# I2C_motor_controller.net
KiCad netlist of a schematic drawn in EAGLE
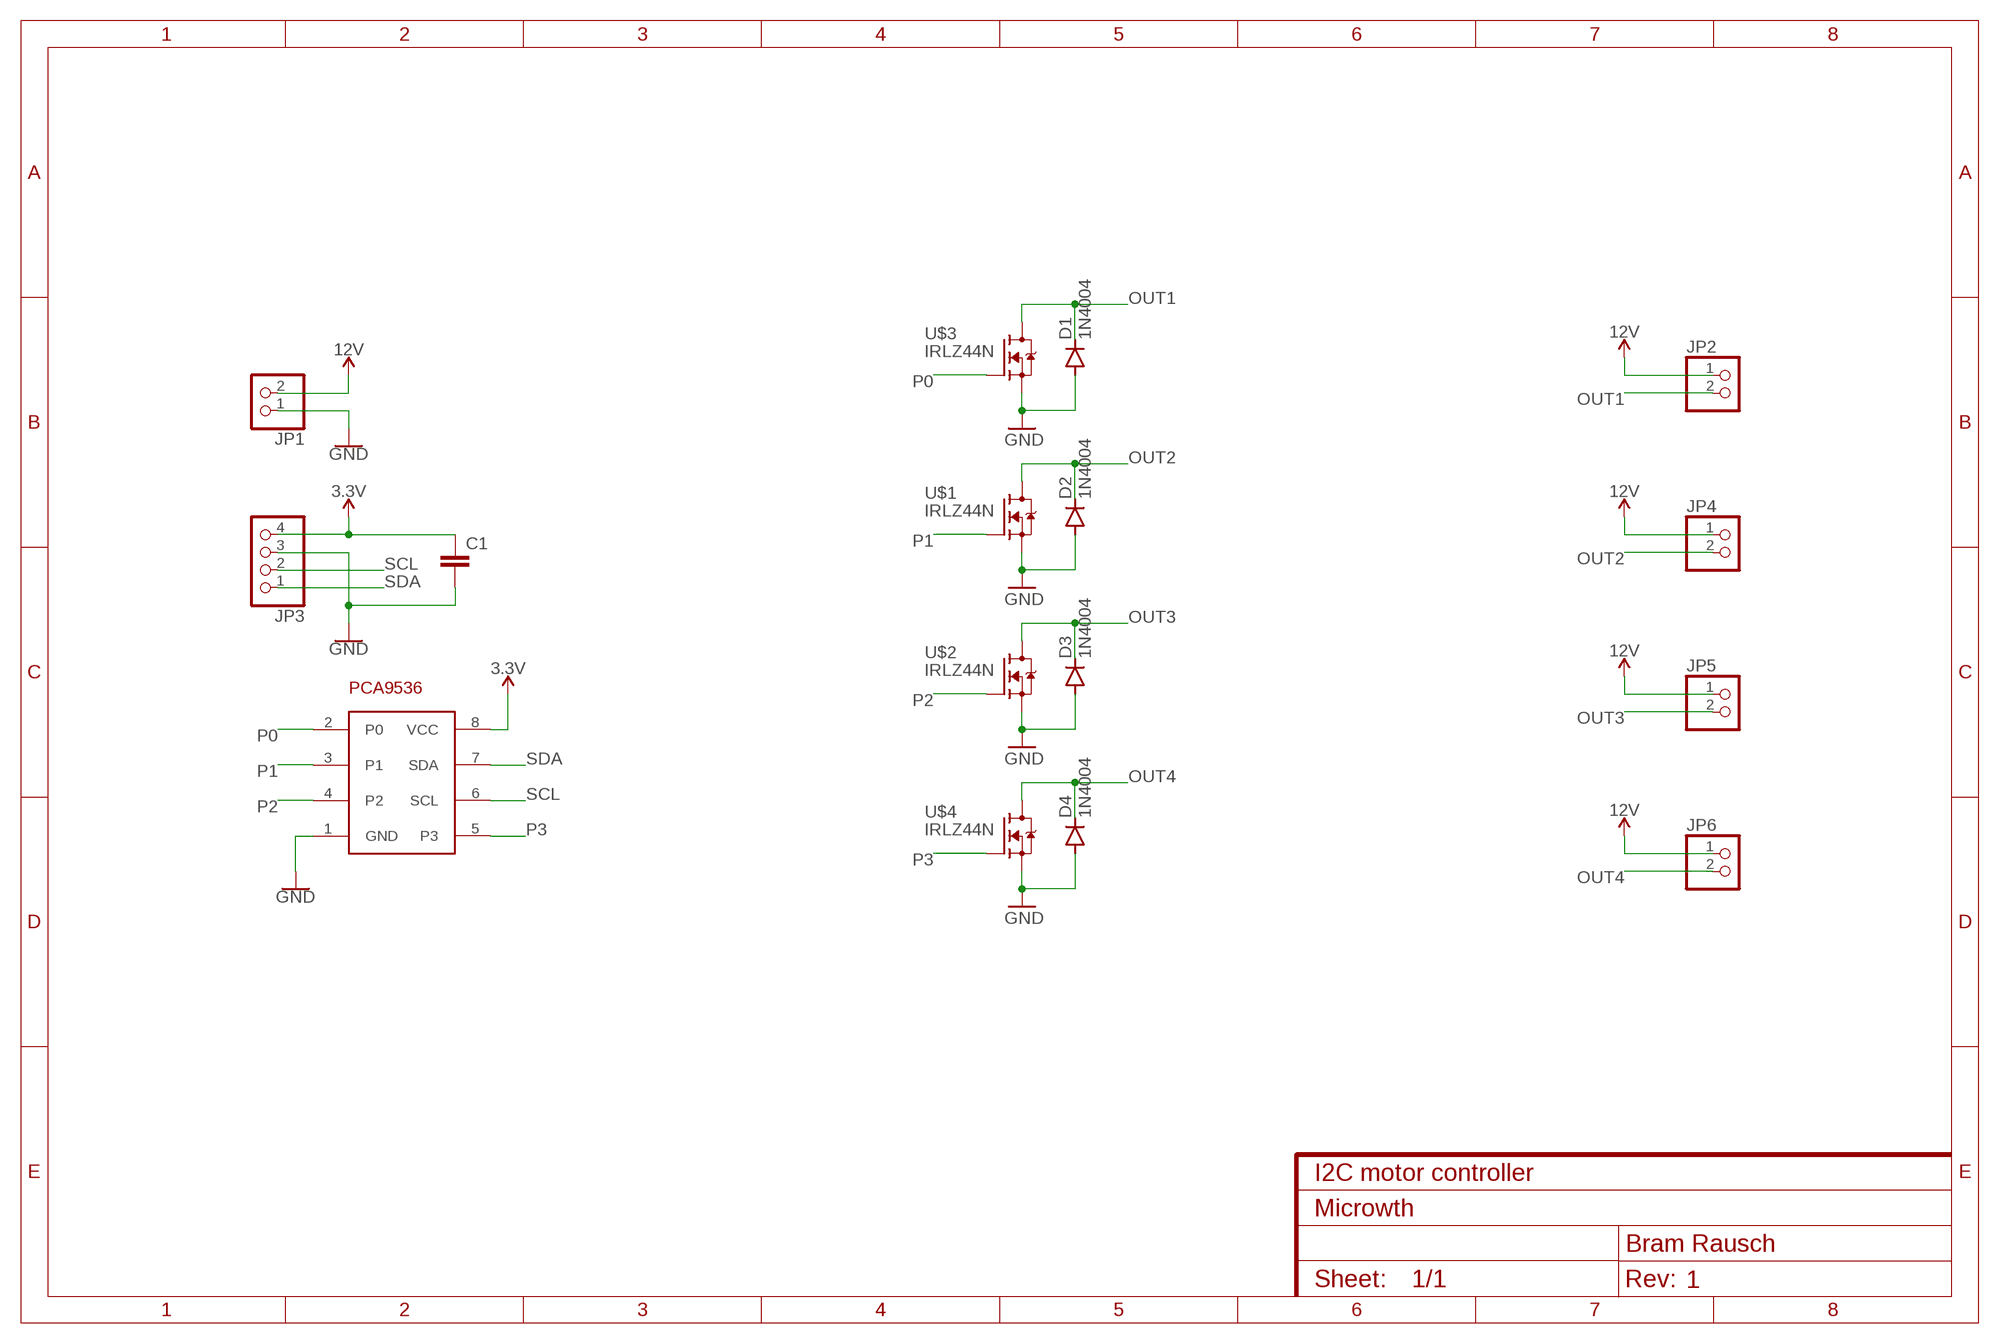
[diagram p0: schematic, sheet 1]

(export (version "E")
  (design (tool "Eeschema 10.0.6"))
  (components
    (comp (ref "C1")
      (value "C-EUC0805")
      (footprint "eagle-import:C0805")
      (libsource (lib "eagle-import") (part "C-EUC0805"))
    )
    (comp (ref "D1")
      (value "1N4004")
      (footprint "eagle-import:DO41-10")
      (libsource (lib "eagle-import") (part "1N4004"))
    )
    (comp (ref "D2")
      (value "1N4004")
      (footprint "eagle-import:DO41-10")
      (libsource (lib "eagle-import") (part "1N4004"))
    )
    (comp (ref "D3")
      (value "1N4004")
      (footprint "eagle-import:DO41-10")
      (libsource (lib "eagle-import") (part "1N4004"))
    )
    (comp (ref "D4")
      (value "1N4004")
      (footprint "eagle-import:DO41-10")
      (libsource (lib "eagle-import") (part "1N4004"))
    )
    (comp (ref "JP1")
      (value "PINHD-1X2")
      (footprint "eagle-import:1X02")
      (libsource (lib "eagle-import") (part "PINHD-1X2"))
    )
    (comp (ref "JP2")
      (value "PINHD-1X2")
      (footprint "eagle-import:1X02")
      (libsource (lib "eagle-import") (part "PINHD-1X2"))
    )
    (comp (ref "JP3")
      (value "PINHD-1X4")
      (footprint "eagle-import:1X04")
      (libsource (lib "eagle-import") (part "PINHD-1X4"))
    )
    (comp (ref "JP4")
      (value "PINHD-1X2")
      (footprint "eagle-import:1X02")
      (libsource (lib "eagle-import") (part "PINHD-1X2"))
    )
    (comp (ref "JP5")
      (value "PINHD-1X2")
      (footprint "eagle-import:1X02")
      (libsource (lib "eagle-import") (part "PINHD-1X2"))
    )
    (comp (ref "JP6")
      (value "PINHD-1X2")
      (footprint "eagle-import:1X02")
      (libsource (lib "eagle-import") (part "PINHD-1X2"))
    )
    (comp (ref "PCA9536")
      (value "PCA9536DGK")
      (footprint "eagle-import:SOP65P490X110-8N")
      (libsource (lib "eagle-import") (part "PCA9536DGK"))
    )
    (comp (ref "U$1")
      (value "IRLZ44N")
      (footprint "eagle-import:TO220")
      (libsource (lib "eagle-import") (part "IRLZ44N"))
    )
    (comp (ref "U$2")
      (value "IRLZ44N")
      (footprint "eagle-import:TO220")
      (libsource (lib "eagle-import") (part "IRLZ44N"))
    )
    (comp (ref "U$3")
      (value "IRLZ44N")
      (footprint "eagle-import:TO220")
      (libsource (lib "eagle-import") (part "IRLZ44N"))
    )
    (comp (ref "U$4")
      (value "IRLZ44N")
      (footprint "eagle-import:TO220")
      (libsource (lib "eagle-import") (part "IRLZ44N"))
    )
  )
  (nets
    (net (code "1") (name "/OUT1") (class "Default")
      (node (ref "D1") (pin "C") (pinfunction "C_C") (pintype "passive"))
      (node (ref "JP2") (pin "2") (pinfunction "2_2") (pintype "passive"))
      (node (ref "U$3") (pin "2") (pinfunction "D_2") (pintype "passive"))
    )
    (net (code "2") (name "/OUT2") (class "Default")
      (node (ref "D2") (pin "C") (pinfunction "C_C") (pintype "passive"))
      (node (ref "JP4") (pin "2") (pinfunction "2_2") (pintype "passive"))
      (node (ref "U$1") (pin "2") (pinfunction "D_2") (pintype "passive"))
    )
    (net (code "3") (name "/OUT3") (class "Default")
      (node (ref "D3") (pin "C") (pinfunction "C_C") (pintype "passive"))
      (node (ref "JP5") (pin "2") (pinfunction "2_2") (pintype "passive"))
      (node (ref "U$2") (pin "2") (pinfunction "D_2") (pintype "passive"))
    )
    (net (code "4") (name "/OUT4") (class "Default")
      (node (ref "D4") (pin "C") (pinfunction "C_C") (pintype "passive"))
      (node (ref "JP6") (pin "2") (pinfunction "2_2") (pintype "passive"))
      (node (ref "U$4") (pin "2") (pinfunction "D_2") (pintype "passive"))
    )
    (net (code "5") (name "/P0") (class "Default")
      (node (ref "PCA9536") (pin "2") (pinfunction "P0_2") (pintype "bidirectional"))
      (node (ref "U$3") (pin "1") (pinfunction "G_1") (pintype "passive"))
    )
    (net (code "6") (name "/P1") (class "Default")
      (node (ref "PCA9536") (pin "3") (pinfunction "P1_3") (pintype "bidirectional"))
      (node (ref "U$1") (pin "1") (pinfunction "G_1") (pintype "passive"))
    )
    (net (code "7") (name "/P2") (class "Default")
      (node (ref "PCA9536") (pin "4") (pinfunction "P2_4") (pintype "bidirectional"))
      (node (ref "U$2") (pin "1") (pinfunction "G_1") (pintype "passive"))
    )
    (net (code "8") (name "/P3") (class "Default")
      (node (ref "PCA9536") (pin "5") (pinfunction "P3_5") (pintype "bidirectional"))
      (node (ref "U$4") (pin "1") (pinfunction "G_1") (pintype "passive"))
    )
    (net (code "9") (name "/SCL") (class "Default")
      (node (ref "JP3") (pin "2") (pinfunction "2_2") (pintype "passive"))
      (node (ref "PCA9536") (pin "6") (pinfunction "SCL_6") (pintype "bidirectional"))
    )
    (net (code "10") (name "/SDA") (class "Default")
      (node (ref "JP3") (pin "1") (pinfunction "1_1") (pintype "passive"))
      (node (ref "PCA9536") (pin "7") (pinfunction "SDA_7") (pintype "bidirectional"))
    )
    (net (code "11") (name "3.3V") (class "Default")
      (node (ref "C1") (pin "1") (pinfunction "1_1") (pintype "passive"))
      (node (ref "JP3") (pin "4") (pinfunction "4_4") (pintype "passive"))
      (node (ref "PCA9536") (pin "8") (pinfunction "VCC_8") (pintype "bidirectional"))
    )
    (net (code "12") (name "12V") (class "Default")
      (node (ref "JP1") (pin "2") (pinfunction "2_2") (pintype "passive"))
      (node (ref "JP2") (pin "1") (pinfunction "1_1") (pintype "passive"))
      (node (ref "JP4") (pin "1") (pinfunction "1_1") (pintype "passive"))
      (node (ref "JP5") (pin "1") (pinfunction "1_1") (pintype "passive"))
      (node (ref "JP6") (pin "1") (pinfunction "1_1") (pintype "passive"))
    )
    (net (code "13") (name "GND") (class "Default")
      (node (ref "C1") (pin "2") (pinfunction "2_2") (pintype "passive"))
      (node (ref "D1") (pin "A") (pinfunction "A_A") (pintype "passive"))
      (node (ref "D2") (pin "A") (pinfunction "A_A") (pintype "passive"))
      (node (ref "D3") (pin "A") (pinfunction "A_A") (pintype "passive"))
      (node (ref "D4") (pin "A") (pinfunction "A_A") (pintype "passive"))
      (node (ref "JP1") (pin "1") (pinfunction "1_1") (pintype "passive"))
      (node (ref "JP3") (pin "3") (pinfunction "3_3") (pintype "passive"))
      (node (ref "PCA9536") (pin "1") (pinfunction "GND_1") (pintype "bidirectional"))
      (node (ref "U$1") (pin "3") (pinfunction "S_3") (pintype "passive"))
      (node (ref "U$2") (pin "3") (pinfunction "S_3") (pintype "passive"))
      (node (ref "U$3") (pin "3") (pinfunction "S_3") (pintype "passive"))
      (node (ref "U$4") (pin "3") (pinfunction "S_3") (pintype "passive"))
    )
  )
)
